# Piezo_array.net
KiCad netlist of a schematic drawn in EAGLE
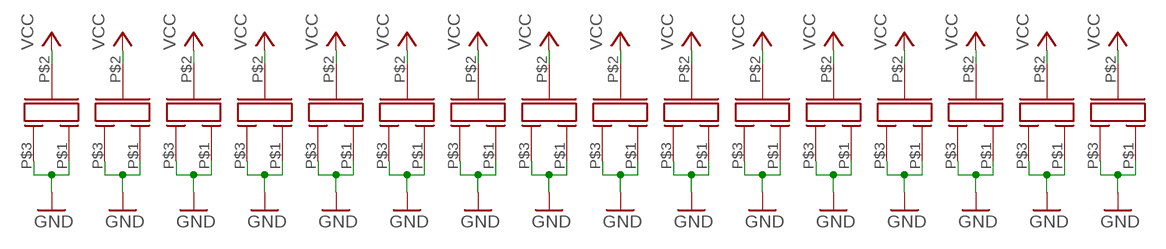
[diagram p0: schematic, sheet 1]

(export (version "E")
  (design (tool "Eeschema 10.0.6"))
  (components
    (comp (ref "U$2")
      (value "PIEZO")
      (footprint "eagle-import:PIEZO")
      (libsource (lib "eagle-import") (part "PIEZO"))
    )
    (comp (ref "U$3")
      (value "PIEZO")
      (footprint "eagle-import:PIEZO")
      (libsource (lib "eagle-import") (part "PIEZO"))
    )
    (comp (ref "U$4")
      (value "PIEZO")
      (footprint "eagle-import:PIEZO")
      (libsource (lib "eagle-import") (part "PIEZO"))
    )
    (comp (ref "U$5")
      (value "PIEZO")
      (footprint "eagle-import:PIEZO")
      (libsource (lib "eagle-import") (part "PIEZO"))
    )
    (comp (ref "U$6")
      (value "PIEZO")
      (footprint "eagle-import:PIEZO")
      (libsource (lib "eagle-import") (part "PIEZO"))
    )
    (comp (ref "U$7")
      (value "PIEZO")
      (footprint "eagle-import:PIEZO")
      (libsource (lib "eagle-import") (part "PIEZO"))
    )
    (comp (ref "U$8")
      (value "PIEZO")
      (footprint "eagle-import:PIEZO")
      (libsource (lib "eagle-import") (part "PIEZO"))
    )
    (comp (ref "U$17")
      (value "PIEZO")
      (footprint "eagle-import:PIEZO")
      (libsource (lib "eagle-import") (part "PIEZO"))
    )
    (comp (ref "U$18")
      (value "PIEZO")
      (footprint "eagle-import:PIEZO")
      (libsource (lib "eagle-import") (part "PIEZO"))
    )
    (comp (ref "U$19")
      (value "PIEZO")
      (footprint "eagle-import:PIEZO")
      (libsource (lib "eagle-import") (part "PIEZO"))
    )
    (comp (ref "U$20")
      (value "PIEZO")
      (footprint "eagle-import:PIEZO")
      (libsource (lib "eagle-import") (part "PIEZO"))
    )
    (comp (ref "U$21")
      (value "PIEZO")
      (footprint "eagle-import:PIEZO")
      (libsource (lib "eagle-import") (part "PIEZO"))
    )
    (comp (ref "U$22")
      (value "PIEZO")
      (footprint "eagle-import:PIEZO")
      (libsource (lib "eagle-import") (part "PIEZO"))
    )
    (comp (ref "U$23")
      (value "PIEZO")
      (footprint "eagle-import:PIEZO")
      (libsource (lib "eagle-import") (part "PIEZO"))
    )
    (comp (ref "U$24")
      (value "PIEZO")
      (footprint "eagle-import:PIEZO")
      (libsource (lib "eagle-import") (part "PIEZO"))
    )
    (comp (ref "U$25")
      (value "PIEZO")
      (footprint "eagle-import:PIEZO")
      (libsource (lib "eagle-import") (part "PIEZO"))
    )
  )
  (nets
    (net (code "1") (name "GND") (class "Default")
      (node (ref "U$17") (pin "P$1") (pinfunction "P$3_P$1") (pintype "bidirectional"))
      (node (ref "U$17") (pin "P$3") (pinfunction "P$2_P$3") (pintype "bidirectional"))
      (node (ref "U$18") (pin "P$1") (pinfunction "P$3_P$1") (pintype "bidirectional"))
      (node (ref "U$18") (pin "P$3") (pinfunction "P$2_P$3") (pintype "bidirectional"))
      (node (ref "U$19") (pin "P$1") (pinfunction "P$3_P$1") (pintype "bidirectional"))
      (node (ref "U$19") (pin "P$3") (pinfunction "P$2_P$3") (pintype "bidirectional"))
      (node (ref "U$2") (pin "P$1") (pinfunction "P$3_P$1") (pintype "bidirectional"))
      (node (ref "U$2") (pin "P$3") (pinfunction "P$2_P$3") (pintype "bidirectional"))
      (node (ref "U$20") (pin "P$1") (pinfunction "P$3_P$1") (pintype "bidirectional"))
      (node (ref "U$20") (pin "P$3") (pinfunction "P$2_P$3") (pintype "bidirectional"))
      (node (ref "U$21") (pin "P$1") (pinfunction "P$3_P$1") (pintype "bidirectional"))
      (node (ref "U$21") (pin "P$3") (pinfunction "P$2_P$3") (pintype "bidirectional"))
      (node (ref "U$22") (pin "P$1") (pinfunction "P$3_P$1") (pintype "bidirectional"))
      (node (ref "U$22") (pin "P$3") (pinfunction "P$2_P$3") (pintype "bidirectional"))
      (node (ref "U$23") (pin "P$1") (pinfunction "P$3_P$1") (pintype "bidirectional"))
      (node (ref "U$23") (pin "P$3") (pinfunction "P$2_P$3") (pintype "bidirectional"))
      (node (ref "U$24") (pin "P$1") (pinfunction "P$3_P$1") (pintype "bidirectional"))
      (node (ref "U$24") (pin "P$3") (pinfunction "P$2_P$3") (pintype "bidirectional"))
      (node (ref "U$25") (pin "P$1") (pinfunction "P$3_P$1") (pintype "bidirectional"))
      (node (ref "U$25") (pin "P$3") (pinfunction "P$2_P$3") (pintype "bidirectional"))
      (node (ref "U$3") (pin "P$1") (pinfunction "P$3_P$1") (pintype "bidirectional"))
      (node (ref "U$3") (pin "P$3") (pinfunction "P$2_P$3") (pintype "bidirectional"))
      (node (ref "U$4") (pin "P$1") (pinfunction "P$3_P$1") (pintype "bidirectional"))
      (node (ref "U$4") (pin "P$3") (pinfunction "P$2_P$3") (pintype "bidirectional"))
      (node (ref "U$5") (pin "P$1") (pinfunction "P$3_P$1") (pintype "bidirectional"))
      (node (ref "U$5") (pin "P$3") (pinfunction "P$2_P$3") (pintype "bidirectional"))
      (node (ref "U$6") (pin "P$1") (pinfunction "P$3_P$1") (pintype "bidirectional"))
      (node (ref "U$6") (pin "P$3") (pinfunction "P$2_P$3") (pintype "bidirectional"))
      (node (ref "U$7") (pin "P$1") (pinfunction "P$3_P$1") (pintype "bidirectional"))
      (node (ref "U$7") (pin "P$3") (pinfunction "P$2_P$3") (pintype "bidirectional"))
      (node (ref "U$8") (pin "P$1") (pinfunction "P$3_P$1") (pintype "bidirectional"))
      (node (ref "U$8") (pin "P$3") (pinfunction "P$2_P$3") (pintype "bidirectional"))
    )
    (net (code "2") (name "VCC") (class "Default")
      (node (ref "U$17") (pin "P$2") (pinfunction "P$1_P$2") (pintype "bidirectional"))
      (node (ref "U$18") (pin "P$2") (pinfunction "P$1_P$2") (pintype "bidirectional"))
      (node (ref "U$19") (pin "P$2") (pinfunction "P$1_P$2") (pintype "bidirectional"))
      (node (ref "U$2") (pin "P$2") (pinfunction "P$1_P$2") (pintype "bidirectional"))
      (node (ref "U$20") (pin "P$2") (pinfunction "P$1_P$2") (pintype "bidirectional"))
      (node (ref "U$21") (pin "P$2") (pinfunction "P$1_P$2") (pintype "bidirectional"))
      (node (ref "U$22") (pin "P$2") (pinfunction "P$1_P$2") (pintype "bidirectional"))
      (node (ref "U$23") (pin "P$2") (pinfunction "P$1_P$2") (pintype "bidirectional"))
      (node (ref "U$24") (pin "P$2") (pinfunction "P$1_P$2") (pintype "bidirectional"))
      (node (ref "U$25") (pin "P$2") (pinfunction "P$1_P$2") (pintype "bidirectional"))
      (node (ref "U$3") (pin "P$2") (pinfunction "P$1_P$2") (pintype "bidirectional"))
      (node (ref "U$4") (pin "P$2") (pinfunction "P$1_P$2") (pintype "bidirectional"))
      (node (ref "U$5") (pin "P$2") (pinfunction "P$1_P$2") (pintype "bidirectional"))
      (node (ref "U$6") (pin "P$2") (pinfunction "P$1_P$2") (pintype "bidirectional"))
      (node (ref "U$7") (pin "P$2") (pinfunction "P$1_P$2") (pintype "bidirectional"))
      (node (ref "U$8") (pin "P$2") (pinfunction "P$1_P$2") (pintype "bidirectional"))
    )
  )
)
